# driver-ha-v3.net
KiCad netlist of a schematic drawn in EAGLE
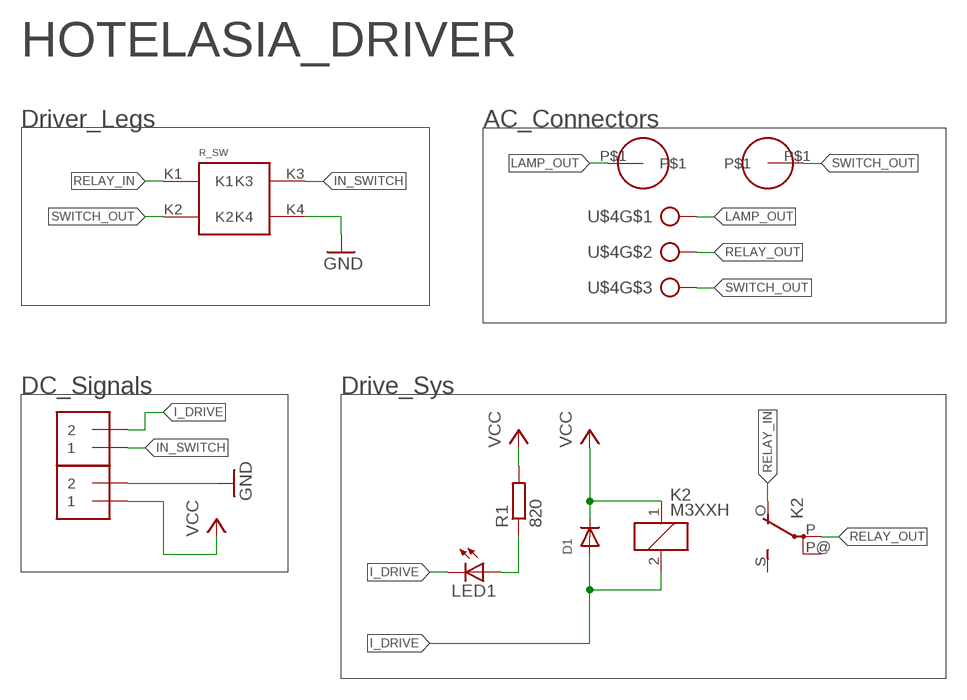
[diagram p0: schematic, sheet 1]

(export (version "E")
  (design (tool "Eeschema 10.0.6"))
  (components
    (comp (ref "D1")
      (value "DIODESMA")
      (footprint "eagle-import:SMADIODE")
      (libsource (lib "eagle-import") (part "DIODESMA"))
    )
    (comp (ref "J1")
      (value "1X2-3.5MM")
      (footprint "eagle-import:1X2-3.5MM")
      (libsource (lib "eagle-import") (part "1X2-3.5MM"))
    )
    (comp (ref "J2")
      (value "1X2-3.5MM")
      (footprint "eagle-import:1X2-3.5MM")
      (libsource (lib "eagle-import") (part "1X2-3.5MM"))
    )
    (comp (ref "K2")
      (value "M3XXH")
      (footprint "eagle-import:M3XXH")
      (libsource (lib "eagle-import") (part "M3XXH"))
    )
    (comp (ref "LED1")
      (value "LEDCHIPLED_0805")
      (footprint "eagle-import:CHIPLED_0805")
      (libsource (lib "eagle-import") (part "LEDCHIPLED_0805"))
    )
    (comp (ref "PAD1")
      (value "ROOM_SWITCH")
      (footprint "eagle-import:ROOM_SWITCH")
      (libsource (lib "eagle-import") (part "ROOM_SWITCH"))
    )
    (comp (ref "R1")
      (value "820")
      (footprint "eagle-import:R0805")
      (libsource (lib "eagle-import") (part "R-EU_R0805"))
    )
    (comp (ref "U$1")
      (value "CONN-CABLE")
      (footprint "eagle-import:CONN-CABLE")
      (libsource (lib "eagle-import") (part "CONN-CABLE"))
    )
    (comp (ref "U$3")
      (value "CONN-CABLE")
      (footprint "eagle-import:CONN-CABLE")
      (libsource (lib "eagle-import") (part "CONN-CABLE"))
    )
    (comp (ref "U$4")
      (value "AK3003")
      (footprint "eagle-import:AK3003")
      (libsource (lib "eagle-import") (part "AK3003"))
    )
  )
  (nets
    (net (code "1") (name "GND") (class "Default")
      (node (ref "J2") (pin "2") (pinfunction "2_2") (pintype "passive"))
      (node (ref "PAD1") (pin "K4") (pinfunction "K4_K4") (pintype "bidirectional"))
    )
    (net (code "2") (name "IN_SWITCH") (class "Default")
      (node (ref "J1") (pin "1") (pinfunction "1_1") (pintype "passive"))
      (node (ref "PAD1") (pin "K3") (pinfunction "K3_K3") (pintype "bidirectional"))
    )
    (net (code "3") (name "I_DRIVE") (class "Default")
      (node (ref "D1") (pin "A") (pinfunction "A_A") (pintype "passive"))
      (node (ref "J1") (pin "2") (pinfunction "2_2") (pintype "passive"))
      (node (ref "K2") (pin "2") (pinfunction "2_2") (pintype "passive"))
      (node (ref "LED1") (pin "C") (pinfunction "C_C") (pintype "passive"))
    )
    (net (code "4") (name "LAMP_OUT") (class "Default")
      (node (ref "U$1") (pin "P$1") (pinfunction "P$1_P$1") (pintype "bidirectional"))
      (node (ref "U$4") (pin "1") (pinfunction "KL_1") (pintype "passive"))
    )
    (net (code "5") (name "Net-(LED1-PadA)") (class "Default")
      (node (ref "LED1") (pin "A") (pinfunction "A_A") (pintype "passive"))
      (node (ref "R1") (pin "1") (pinfunction "1_1") (pintype "passive"))
    )
    (net (code "6") (name "RELAY_IN") (class "Default")
      (node (ref "K2") (pin "O") (pinfunction "O_O") (pintype "passive"))
      (node (ref "PAD1") (pin "K1") (pinfunction "K1_K1") (pintype "bidirectional"))
    )
    (net (code "7") (name "RELAY_OUT") (class "Default")
      (node (ref "K2") (pin "P") (pinfunction "P_P") (pintype "passive"))
      (node (ref "U$4") (pin "2") (pinfunction "KL_2") (pintype "passive"))
    )
    (net (code "8") (name "SWITCH_OUT") (class "Default")
      (node (ref "PAD1") (pin "K2") (pinfunction "K2_K2") (pintype "bidirectional"))
      (node (ref "U$3") (pin "P$1") (pinfunction "P$1_P$1") (pintype "bidirectional"))
      (node (ref "U$4") (pin "3") (pinfunction "KL_3") (pintype "passive"))
    )
    (net (code "9") (name "VCC") (class "Default")
      (node (ref "D1") (pin "C") (pinfunction "C_C") (pintype "passive"))
      (node (ref "J2") (pin "1") (pinfunction "1_1") (pintype "passive"))
      (node (ref "K2") (pin "1") (pinfunction "1_1") (pintype "passive"))
      (node (ref "R1") (pin "2") (pinfunction "2_2") (pintype "passive"))
    )
    (net (code "10") (name "unconnected-(K2-PadS)") (class "Default")
      (node (ref "K2") (pin "S") (pinfunction "S_S") (pintype "passive"))
    )
    (net (code "11") (name "unconnected-(K2B-P-PadP@)") (class "Default")
      (node (ref "K2") (pin "P@") (pinfunction "P_P@") (pintype "passive"))
    )
  )
)
